# Schematic.net
KiCad netlist of a schematic drawn in EAGLE
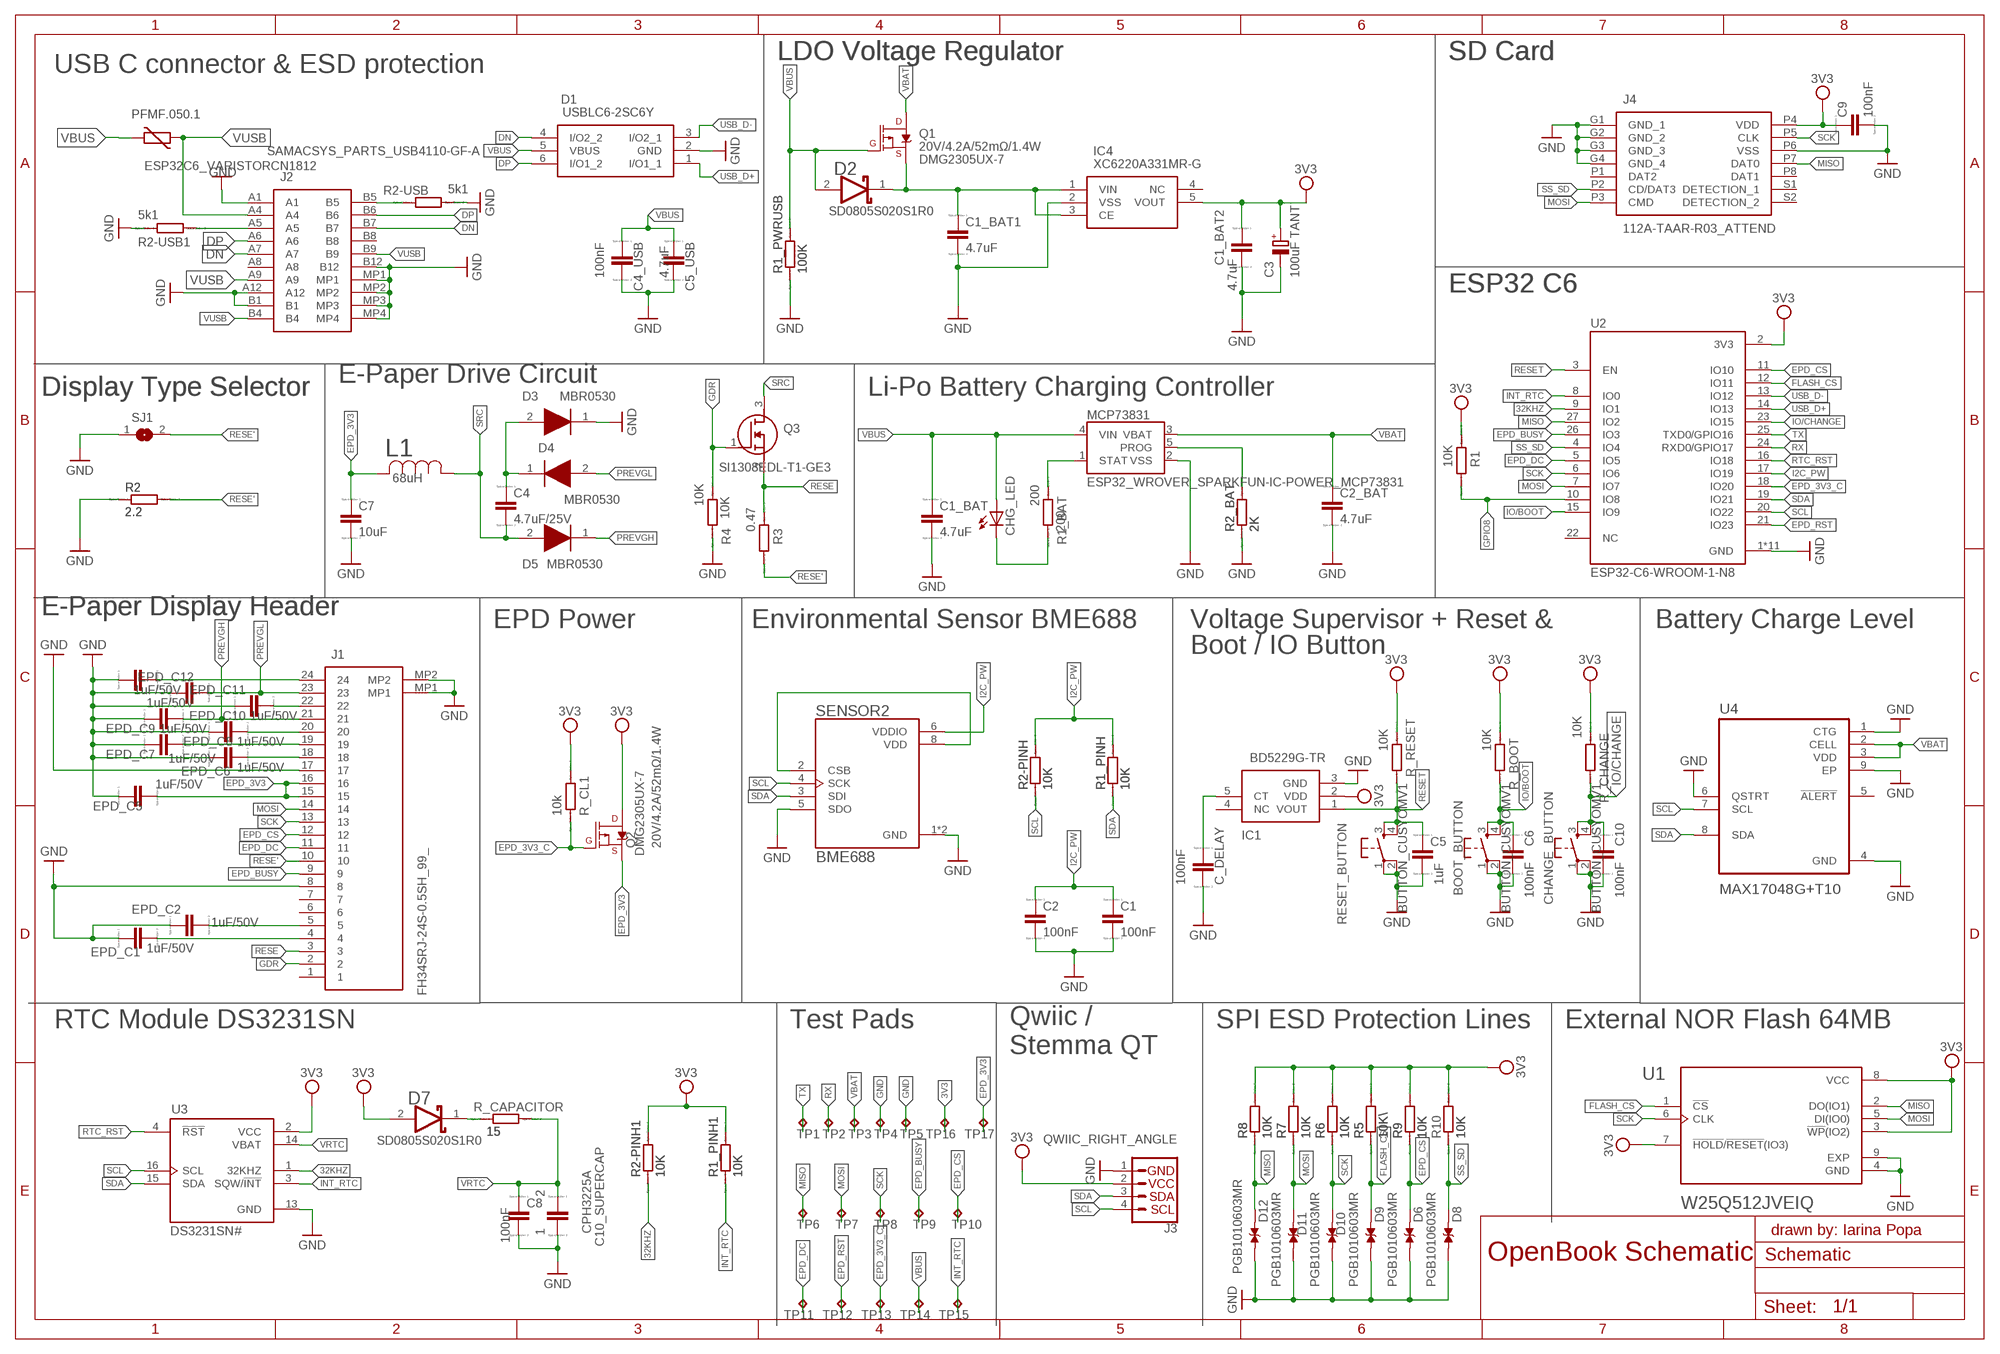
[diagram p0: schematic, sheet 1]

(export (version "E")
  (design (tool "Eeschema 10.0.6"))
  (components
    (comp (ref "BOOT_BUTTON")
      (value "BUTTON_CUSYOMV1")
      (footprint "eagle-import:MYBUTTON")
      (libsource (lib "eagle-import") (part "BUTTON_CUSYOMV1"))
    )
    (comp (ref "C1")
      (value "100nF")
      (footprint "eagle-import:EAGLE-LTSPICE_C0402")
      (libsource (lib "eagle-import") (part "EAGLE-LTSPICE_CC0402"))
    )
    (comp (ref "C1_BAT")
      (value "4.7uF")
      (footprint "eagle-import:EAGLE-LTSPICE_C0402")
      (libsource (lib "eagle-import") (part "EAGLE-LTSPICE_CC0402"))
    )
    (comp (ref "C1_BAT1")
      (value "4.7uF")
      (footprint "eagle-import:EAGLE-LTSPICE_C0402")
      (libsource (lib "eagle-import") (part "EAGLE-LTSPICE_CC0402"))
    )
    (comp (ref "C1_BAT2")
      (value "4.7uF")
      (footprint "eagle-import:EAGLE-LTSPICE_C0402")
      (libsource (lib "eagle-import") (part "EAGLE-LTSPICE_CC0402"))
    )
    (comp (ref "C2")
      (value "100nF")
      (footprint "eagle-import:EAGLE-LTSPICE_C0402")
      (libsource (lib "eagle-import") (part "EAGLE-LTSPICE_CC0402"))
    )
    (comp (ref "C2_BAT")
      (value "4.7uF")
      (footprint "eagle-import:EAGLE-LTSPICE_C0402")
      (libsource (lib "eagle-import") (part "EAGLE-LTSPICE_CC0402"))
    )
    (comp (ref "C3")
      (value "100uF TANT")
      (footprint "eagle-import:RCL_CT3528")
      (libsource (lib "eagle-import") (part "RCL_CPOL-EUCT3528"))
    )
    (comp (ref "C4")
      (value "4.7uF/25V")
      (footprint "eagle-import:EAGLE-LTSPICE_C0402")
      (libsource (lib "eagle-import") (part "EAGLE-LTSPICE_CC0402"))
    )
    (comp (ref "C4_USB")
      (value "100nF")
      (footprint "eagle-import:EAGLE-LTSPICE_C0402")
      (libsource (lib "eagle-import") (part "EAGLE-LTSPICE_CC0402"))
    )
    (comp (ref "C5")
      (value "1uF")
      (footprint "eagle-import:EAGLE-LTSPICE_C0402")
      (libsource (lib "eagle-import") (part "EAGLE-LTSPICE_CC0402"))
    )
    (comp (ref "C5_USB")
      (value "4.7uF")
      (footprint "eagle-import:EAGLE-LTSPICE_C0402")
      (libsource (lib "eagle-import") (part "EAGLE-LTSPICE_CC0402"))
    )
    (comp (ref "C6")
      (value "100nF")
      (footprint "eagle-import:EAGLE-LTSPICE_C0402")
      (libsource (lib "eagle-import") (part "EAGLE-LTSPICE_CC0402"))
    )
    (comp (ref "C7")
      (value "10uF")
      (footprint "eagle-import:EAGLE-LTSPICE_C0402")
      (libsource (lib "eagle-import") (part "EAGLE-LTSPICE_CC0402"))
    )
    (comp (ref "C8")
      (value "100nF")
      (footprint "eagle-import:EAGLE-LTSPICE_C0402")
      (libsource (lib "eagle-import") (part "EAGLE-LTSPICE_CC0402"))
    )
    (comp (ref "C9")
      (value "100nF")
      (footprint "eagle-import:EAGLE-LTSPICE_C0402")
      (libsource (lib "eagle-import") (part "EAGLE-LTSPICE_CC0402"))
    )
    (comp (ref "C10")
      (value "100nF")
      (footprint "eagle-import:EAGLE-LTSPICE_C0402")
      (libsource (lib "eagle-import") (part "EAGLE-LTSPICE_CC0402"))
    )
    (comp (ref "C10_SUPERCAP")
      (value "CPH3225A")
      (footprint "eagle-import:EAGLE-LTSPICE_C0402")
      (libsource (lib "eagle-import") (part "EAGLE-LTSPICE_CC0402"))
    )
    (comp (ref "CHANGE_BUTTON")
      (value "BUTTON_CUSYOMV1")
      (footprint "eagle-import:MYBUTTON")
      (libsource (lib "eagle-import") (part "BUTTON_CUSYOMV1"))
    )
    (comp (ref "CHG_LED")
      (value "ADAFRUIT_LEDCHIP-LED0603")
      (footprint "eagle-import:ADAFRUIT_CHIP-LED0603")
      (libsource (lib "eagle-import") (part "ADAFRUIT_LEDCHIP-LED0603"))
    )
    (comp (ref "C_DELAY")
      (value "100nF")
      (footprint "eagle-import:EAGLE-LTSPICE_C0402")
      (libsource (lib "eagle-import") (part "EAGLE-LTSPICE_CC0402"))
    )
    (comp (ref "D1")
      (value "USBLC6-2SC6Y")
      (footprint "eagle-import:SOT95P280X145-6N")
      (fields (field (name "MF") "STMicroelectronics"))
      (libsource (lib "eagle-import") (part "USBLC6-2SC6Y"))
    )
    (comp (ref "D2")
      (value "ESP32_WROVER_AVX---SD0805S020S1R0_AVX_SD0805S020S1R0_0_0AVX_SD0805S020S1R0_0_0")
      (footprint "eagle-import:ESP32_WROVER_AVX---SD0805S020S1R0_AVX_SD0805S020S1R0_0")
      (fields
        (field (name "DIGIKEY_PART_NUMBER") "478-7800-1-ND")
        (field (name "MF") "AVX")
        (field (name "MOUSER_PART_NUMBER") "581-SD0805S020S1R0")
      )
      (libsource (lib "eagle-import") (part "ESP32_WROVER_AVX---SD0805S020S1R0_AVX_SD0805S020S1R0_0_0AVX_SD0805S020S1R0_0_0"))
    )
    (comp (ref "D3")
      (value "MBR0530")
      (footprint "eagle-import:SOD3716X135N")
      (fields (field (name "MF") "ON Semiconductor"))
      (libsource (lib "eagle-import") (part "MBR0530"))
    )
    (comp (ref "D4")
      (value "MBR0530")
      (footprint "eagle-import:SOD3716X135N")
      (fields (field (name "MF") "ON Semiconductor"))
      (libsource (lib "eagle-import") (part "MBR0530"))
    )
    (comp (ref "D5")
      (value "MBR0530")
      (footprint "eagle-import:SOD3716X135N")
      (fields (field (name "MF") "ON Semiconductor"))
      (libsource (lib "eagle-import") (part "MBR0530"))
    )
    (comp (ref "D6")
      (value "PGB1010603MR")
      (footprint "eagle-import:DIOC1608X36N")
      (fields (field (name "MF") "Littelfuse Inc."))
      (libsource (lib "eagle-import") (part "PGB1010603MR"))
    )
    (comp (ref "D7")
      (value "ESP32_WROVER_AVX---SD0805S020S1R0_AVX_SD0805S020S1R0_0_0AVX_SD0805S020S1R0_0_0")
      (footprint "eagle-import:ESP32_WROVER_AVX---SD0805S020S1R0_AVX_SD0805S020S1R0_0")
      (fields
        (field (name "DIGIKEY_PART_NUMBER") "478-7800-1-ND")
        (field (name "MF") "AVX")
        (field (name "MOUSER_PART_NUMBER") "581-SD0805S020S1R0")
      )
      (libsource (lib "eagle-import") (part "ESP32_WROVER_AVX---SD0805S020S1R0_AVX_SD0805S020S1R0_0_0AVX_SD0805S020S1R0_0_0"))
    )
    (comp (ref "D8")
      (value "PGB1010603MR")
      (footprint "eagle-import:DIOC1608X36N")
      (fields (field (name "MF") "Littelfuse Inc."))
      (libsource (lib "eagle-import") (part "PGB1010603MR"))
    )
    (comp (ref "D9")
      (value "PGB1010603MR")
      (footprint "eagle-import:DIOC1608X36N")
      (fields (field (name "MF") "Littelfuse Inc."))
      (libsource (lib "eagle-import") (part "PGB1010603MR"))
    )
    (comp (ref "D10")
      (value "PGB1010603MR")
      (footprint "eagle-import:DIOC1608X36N")
      (fields (field (name "MF") "Littelfuse Inc."))
      (libsource (lib "eagle-import") (part "PGB1010603MR"))
    )
    (comp (ref "D11")
      (value "PGB1010603MR")
      (footprint "eagle-import:DIOC1608X36N")
      (fields (field (name "MF") "Littelfuse Inc."))
      (libsource (lib "eagle-import") (part "PGB1010603MR"))
    )
    (comp (ref "D12")
      (value "PGB1010603MR")
      (footprint "eagle-import:DIOC1608X36N")
      (fields (field (name "MF") "Littelfuse Inc."))
      (libsource (lib "eagle-import") (part "PGB1010603MR"))
    )
    (comp (ref "EPD_C1")
      (value "1uF/50V")
      (footprint "eagle-import:EAGLE-LTSPICE_C0402")
      (libsource (lib "eagle-import") (part "EAGLE-LTSPICE_CC0402"))
    )
    (comp (ref "EPD_C2")
      (value "1uF/50V")
      (footprint "eagle-import:EAGLE-LTSPICE_C0402")
      (libsource (lib "eagle-import") (part "EAGLE-LTSPICE_CC0402"))
    )
    (comp (ref "EPD_C5")
      (value "1uF/50V")
      (footprint "eagle-import:EAGLE-LTSPICE_C0402")
      (libsource (lib "eagle-import") (part "EAGLE-LTSPICE_CC0402"))
    )
    (comp (ref "EPD_C6")
      (value "1uF/50V")
      (footprint "eagle-import:EAGLE-LTSPICE_C0402")
      (libsource (lib "eagle-import") (part "EAGLE-LTSPICE_CC0402"))
    )
    (comp (ref "EPD_C7")
      (value "1uF/50V")
      (footprint "eagle-import:EAGLE-LTSPICE_C0402")
      (libsource (lib "eagle-import") (part "EAGLE-LTSPICE_CC0402"))
    )
    (comp (ref "EPD_C8")
      (value "1uF/50V")
      (footprint "eagle-import:EAGLE-LTSPICE_C0402")
      (libsource (lib "eagle-import") (part "EAGLE-LTSPICE_CC0402"))
    )
    (comp (ref "EPD_C9")
      (value "1uF/50V")
      (footprint "eagle-import:EAGLE-LTSPICE_C0402")
      (libsource (lib "eagle-import") (part "EAGLE-LTSPICE_CC0402"))
    )
    (comp (ref "EPD_C10")
      (value "1uF/50V")
      (footprint "eagle-import:EAGLE-LTSPICE_C0402")
      (libsource (lib "eagle-import") (part "EAGLE-LTSPICE_CC0402"))
    )
    (comp (ref "EPD_C11")
      (value "1uF/50V")
      (footprint "eagle-import:EAGLE-LTSPICE_C0402")
      (libsource (lib "eagle-import") (part "EAGLE-LTSPICE_CC0402"))
    )
    (comp (ref "EPD_C12")
      (value "1uF/50V")
      (footprint "eagle-import:EAGLE-LTSPICE_C0402")
      (libsource (lib "eagle-import") (part "EAGLE-LTSPICE_CC0402"))
    )
    (comp (ref "IC1")
      (value "BD5229G-TR")
      (footprint "eagle-import:SOT95P280X125-5N")
      (fields (field (name "MOUSER_PART_NUMBER") "755-BD5229G-TR"))
      (libsource (lib "eagle-import") (part "BD5229G-TR"))
    )
    (comp (ref "IC4")
      (value "XC6220A331MR-G")
      (footprint "eagle-import:SOT95P280X120-5N")
      (fields (field (name "MOUSER_PART_NUMBER") "865-XC6220A331MR-G"))
      (libsource (lib "eagle-import") (part "XC6220A331MR-G"))
    )
    (comp (ref "J1")
      (value "FH34SRJ-24S-0.5SH_99_")
      (footprint "eagle-import:FH34SRJ24S05SH99")
      (fields
        (field (name "MANUFACTURER_PART_NUMBER") "FH34SRJ-24S-0.5SH(99)")
        (field (name "MOUSER_PART_NUMBER") "798-FH34SRJ24S05SH99")
      )
      (libsource (lib "eagle-import") (part "FH34SRJ-24S-0.5SH_99_"))
    )
    (comp (ref "J2")
      (value "SAMACSYS_PARTS_USB4110-GF-A")
      (footprint "eagle-import:SAMACSYS_PARTS_USB4110GFA")
      (fields
        (field (name "MANUFACTURER_PART_NUMBER") "USB4110-GF-A")
        (field (name "MOUSER_PART_NUMBER") "640-USB4110-GF-A")
      )
      (libsource (lib "eagle-import") (part "SAMACSYS_PARTS_USB4110-GF-A"))
    )
    (comp (ref "J3")
      (value "QWIIC_RIGHT_ANGLE")
      (footprint "eagle-import:JST04_1MM_RA")
      (libsource (lib "eagle-import") (part "QWIIC_CONNECTORJS-1MM"))
    )
    (comp (ref "J4")
      (value "112A-TAAR-R03_ATTEND")
      (footprint "eagle-import:112ATAARR03ATTEND")
      (fields (field (name "MANUFACTURER_PART_NUMBER") "112A-TAAR-R03 ATTEND"))
      (libsource (lib "eagle-import") (part "112A-TAAR-R03_ATTEND"))
    )
    (comp (ref "L1")
      (value "68uH")
      (footprint "eagle-import:IND_4828-WE-TPC_WRE")
      (fields
        (field (name "MANUFACTURER_PART_NUMBER") "744043680")
        (field (name "COPYRIGHT") "Copyright (C) 2024 Ultra Librarian. All rights reserved.")
      )
      (libsource (lib "eagle-import") (part "744043680IND_4828-WE-TPC_WRE"))
    )
    (comp (ref "MCP73831")
      (value "ESP32_WROVER_SPARKFUN-IC-POWER_MCP73831")
      (footprint "eagle-import:ESP32_WROVER_SPARKFUN-IC-POWER_SOT23-5")
      (libsource (lib "eagle-import") (part "ESP32_WROVER_SPARKFUN-IC-POWER_MCP73831"))
    )
    (comp (ref "PFMF.050.1")
      (value "ESP32C6_VARISTORCN1812")
      (footprint "eagle-import:ESP32C6_VARISTOR_CT_CN1812")
      (libsource (lib "eagle-import") (part "ESP32C6_VARISTORCN1812"))
    )
    (comp (ref "Q1")
      (value "20V/4.2A/52mΩ/1.4W")
      (footprint "eagle-import:ESP32_WROVER_SPARKFUN-DISCRETESEMI_SOT23-3")
      (libsource (lib "eagle-import") (part "ESP32_WROVER_SPARKFUN-DISCRETESEMI_MOSFET_PCH-DMG2305UX-7"))
    )
    (comp (ref "Q2")
      (value "20V/4.2A/52mΩ/1.4W")
      (footprint "eagle-import:ESP32_WROVER_SPARKFUN-DISCRETESEMI_SOT23-3")
      (libsource (lib "eagle-import") (part "ESP32_WROVER_SPARKFUN-DISCRETESEMI_MOSFET_PCH-DMG2305UX-7"))
    )
    (comp (ref "Q3")
      (value "SI1308EDL-T1-GE3")
      (footprint "eagle-import:SOT65P210X110-3N")
      (fields (field (name "MF") "Vishay Siliconix"))
      (libsource (lib "eagle-import") (part "SI1308EDL-T1-GE3"))
    )
    (comp (ref "R1")
      (value "10K")
      (footprint "eagle-import:ESP32_WROVER_EAGLE-LTSPICE_R0402")
      (libsource (lib "eagle-import") (part "ESP32_WROVER_EAGLE-LTSPICE_RR0402"))
    )
    (comp (ref "R1_BAT")
      (value "200")
      (footprint "eagle-import:ESP32_WROVER_EAGLE-LTSPICE_R0402")
      (libsource (lib "eagle-import") (part "ESP32_WROVER_EAGLE-LTSPICE_RR0402"))
    )
    (comp (ref "R1_PINH")
      (value "10K")
      (footprint "eagle-import:ESP32_WROVER_EAGLE-LTSPICE_R0402")
      (libsource (lib "eagle-import") (part "ESP32_WROVER_EAGLE-LTSPICE_RR0402"))
    )
    (comp (ref "R1_PINH1")
      (value "10K")
      (footprint "eagle-import:ESP32_WROVER_EAGLE-LTSPICE_R0402")
      (libsource (lib "eagle-import") (part "ESP32_WROVER_EAGLE-LTSPICE_RR0402"))
    )
    (comp (ref "R1_PWRUSB")
      (value "100K")
      (footprint "eagle-import:ESP32_WROVER_EAGLE-LTSPICE_R0402")
      (libsource (lib "eagle-import") (part "ESP32_WROVER_EAGLE-LTSPICE_RR0402"))
    )
    (comp (ref "R2")
      (value "2.2")
      (footprint "eagle-import:ESP32_WROVER_EAGLE-LTSPICE_R0402")
      (libsource (lib "eagle-import") (part "ESP32_WROVER_EAGLE-LTSPICE_RR0402"))
    )
    (comp (ref "R2-PINH")
      (value "10K")
      (footprint "eagle-import:ESP32_WROVER_EAGLE-LTSPICE_R0402")
      (libsource (lib "eagle-import") (part "ESP32_WROVER_EAGLE-LTSPICE_RR0402"))
    )
    (comp (ref "R2-PINH1")
      (value "10K")
      (footprint "eagle-import:ESP32_WROVER_EAGLE-LTSPICE_R0402")
      (libsource (lib "eagle-import") (part "ESP32_WROVER_EAGLE-LTSPICE_RR0402"))
    )
    (comp (ref "R2-USB")
      (value "5k1")
      (footprint "eagle-import:ESP32_WROVER_EAGLE-LTSPICE_R0402")
      (libsource (lib "eagle-import") (part "ESP32_WROVER_EAGLE-LTSPICE_RR0402"))
    )
    (comp (ref "R2-USB1")
      (value "5k1")
      (footprint "eagle-import:ESP32_WROVER_EAGLE-LTSPICE_R0402")
      (libsource (lib "eagle-import") (part "ESP32_WROVER_EAGLE-LTSPICE_RR0402"))
    )
    (comp (ref "R2_BAT")
      (value "2K")
      (footprint "eagle-import:ESP32_WROVER_EAGLE-LTSPICE_R0402")
      (libsource (lib "eagle-import") (part "ESP32_WROVER_EAGLE-LTSPICE_RR0402"))
    )
    (comp (ref "R3")
      (value "0.47")
      (footprint "eagle-import:ESP32_WROVER_EAGLE-LTSPICE_R0402")
      (libsource (lib "eagle-import") (part "ESP32_WROVER_EAGLE-LTSPICE_RR0402"))
    )
    (comp (ref "R4")
      (value "10K")
      (footprint "eagle-import:ESP32_WROVER_EAGLE-LTSPICE_R0402")
      (libsource (lib "eagle-import") (part "ESP32_WROVER_EAGLE-LTSPICE_RR0402"))
    )
    (comp (ref "R5")
      (value "10K\\")
      (footprint "eagle-import:ESP32_WROVER_EAGLE-LTSPICE_R0402")
      (libsource (lib "eagle-import") (part "ESP32_WROVER_EAGLE-LTSPICE_RR0402"))
    )
    (comp (ref "R6")
      (value "10K")
      (footprint "eagle-import:ESP32_WROVER_EAGLE-LTSPICE_R0402")
      (libsource (lib "eagle-import") (part "ESP32_WROVER_EAGLE-LTSPICE_RR0402"))
    )
    (comp (ref "R7")
      (value "10K")
      (footprint "eagle-import:ESP32_WROVER_EAGLE-LTSPICE_R0402")
      (libsource (lib "eagle-import") (part "ESP32_WROVER_EAGLE-LTSPICE_RR0402"))
    )
    (comp (ref "R8")
      (value "10K")
      (footprint "eagle-import:ESP32_WROVER_EAGLE-LTSPICE_R0402")
      (libsource (lib "eagle-import") (part "ESP32_WROVER_EAGLE-LTSPICE_RR0402"))
    )
    (comp (ref "R9")
      (value "10K")
      (footprint "eagle-import:ESP32_WROVER_EAGLE-LTSPICE_R0402")
      (libsource (lib "eagle-import") (part "ESP32_WROVER_EAGLE-LTSPICE_RR0402"))
    )
    (comp (ref "R10")
      (value "10K")
      (footprint "eagle-import:ESP32_WROVER_EAGLE-LTSPICE_R0402")
      (libsource (lib "eagle-import") (part "ESP32_WROVER_EAGLE-LTSPICE_RR0402"))
    )
    (comp (ref "RESET_BUTTON")
      (value "BUTTON_CUSYOMV1")
      (footprint "eagle-import:MYBUTTON")
      (libsource (lib "eagle-import") (part "BUTTON_CUSYOMV1"))
    )
    (comp (ref "R_BOOT")
      (value "10K")
      (footprint "eagle-import:ESP32_WROVER_EAGLE-LTSPICE_R0402")
      (libsource (lib "eagle-import") (part "ESP32_WROVER_EAGLE-LTSPICE_RR0402"))
    )
    (comp (ref "R_CAPACITOR")
      (value "15")
      (footprint "eagle-import:ESP32_WROVER_EAGLE-LTSPICE_R0402")
      (libsource (lib "eagle-import") (part "ESP32_WROVER_EAGLE-LTSPICE_RR0402"))
    )
    (comp (ref "R_CHANGE")
      (value "10K")
      (footprint "eagle-import:ESP32_WROVER_EAGLE-LTSPICE_R0402")
      (libsource (lib "eagle-import") (part "ESP32_WROVER_EAGLE-LTSPICE_RR0402"))
    )
    (comp (ref "R_CL1")
      (value "10k")
      (footprint "eagle-import:ESP32_WROVER_EAGLE-LTSPICE_R0402")
      (libsource (lib "eagle-import") (part "ESP32_WROVER_EAGLE-LTSPICE_RR0402"))
    )
    (comp (ref "R_RESET")
      (value "10K")
      (footprint "eagle-import:ESP32_WROVER_EAGLE-LTSPICE_R0402")
      (libsource (lib "eagle-import") (part "ESP32_WROVER_EAGLE-LTSPICE_RR0402"))
    )
    (comp (ref "SENSOR2")
      (value "BME688")
      (footprint "eagle-import:ESP32_WROVER_BME680_PSON80P300X300X100-8N")
      (fields (field (name "MF") "Bosch Sensortec") (field (name "MP") "BME680"))
      (libsource (lib "eagle-import") (part "ESP32_WROVER_BME680_BME680"))
    )
    (comp (ref "SJ1") (value "SJ") (footprint "eagle-import:SJ") (libsource (lib "eagle-import") (part "SJ")))
    (comp (ref "TP1")
      (value "TPTP20R")
      (footprint "eagle-import:TP20R")
      (libsource (lib "eagle-import") (part "TPTP20R"))
    )
    (comp (ref "TP2")
      (value "TPTP20R")
      (footprint "eagle-import:TP20R")
      (libsource (lib "eagle-import") (part "TPTP20R"))
    )
    (comp (ref "TP3")
      (value "TPTP20R")
      (footprint "eagle-import:TP20R")
      (libsource (lib "eagle-import") (part "TPTP20R"))
    )
    (comp (ref "TP4")
      (value "TPTP20R")
      (footprint "eagle-import:TP20R")
      (libsource (lib "eagle-import") (part "TPTP20R"))
    )
    (comp (ref "TP5")
      (value "TPTP20R")
      (footprint "eagle-import:TP20R")
      (libsource (lib "eagle-import") (part "TPTP20R"))
    )
    (comp (ref "TP6")
      (value "TPTP20R")
      (footprint "eagle-import:TP20R")
      (libsource (lib "eagle-import") (part "TPTP20R"))
    )
    (comp (ref "TP7")
      (value "TPTP20R")
      (footprint "eagle-import:TP20R")
      (libsource (lib "eagle-import") (part "TPTP20R"))
    )
    (comp (ref "TP8")
      (value "TPTP20R")
      (footprint "eagle-import:TP20R")
      (libsource (lib "eagle-import") (part "TPTP20R"))
    )
    (comp (ref "TP9")
      (value "TPTP20R")
      (footprint "eagle-import:TP20R")
      (libsource (lib "eagle-import") (part "TPTP20R"))
    )
    (comp (ref "TP10")
      (value "TPTP20R")
      (footprint "eagle-import:TP20R")
      (libsource (lib "eagle-import") (part "TPTP20R"))
    )
    (comp (ref "TP11")
      (value "TPTP20R")
      (footprint "eagle-import:TP20R")
      (libsource (lib "eagle-import") (part "TPTP20R"))
    )
    (comp (ref "TP12")
      (value "TPTP20R")
      (footprint "eagle-import:TP20R")
      (libsource (lib "eagle-import") (part "TPTP20R"))
    )
    (comp (ref "TP13")
      (value "TPTP20R")
      (footprint "eagle-import:TP20R")
      (libsource (lib "eagle-import") (part "TPTP20R"))
    )
    (comp (ref "TP14")
      (value "TPTP20R")
      (footprint "eagle-import:TP20R")
      (libsource (lib "eagle-import") (part "TPTP20R"))
    )
    (comp (ref "TP15")
      (value "TPTP20R")
      (footprint "eagle-import:TP20R")
      (libsource (lib "eagle-import") (part "TPTP20R"))
    )
    (comp (ref "TP16")
      (value "TPTP20R")
      (footprint "eagle-import:TP20R")
      (libsource (lib "eagle-import") (part "TPTP20R"))
    )
    (comp (ref "TP17")
      (value "TPTP20R")
      (footprint "eagle-import:TP20R")
      (libsource (lib "eagle-import") (part "TPTP20R"))
    )
    (comp (ref "U1")
      (value "W25Q512JVEIQ")
      (footprint "eagle-import:SON127P600X800X80-9N")
      (fields (field (name "MF") "Winbond Electronics"))
      (libsource (lib "eagle-import") (part "W25Q512JVEIQ"))
    )
    (comp (ref "U2")
      (value "ESP32-C6-WROOM-1-N8")
      (footprint "eagle-import:XCVR_ESP32-C6-WROOM-1-N8")
      (fields (field (name "MF") "Espressif Systems"))
      (libsource (lib "eagle-import") (part "ESP32-C6-WROOM-1-N8"))
    )
    (comp (ref "U3")
      (value "DS3231SN#")
      (footprint "eagle-import:SOIC127P1032X265-16N")
      (fields (field (name "MF") "Analog Devices"))
      (libsource (lib "eagle-import") (part "DS3231SN#"))
    )
    (comp (ref "U4")
      (value "MAX17048G+T10")
      (footprint "eagle-import:SON50P200X200X80-9N")
      (fields (field (name "MF") "Analog Devices"))
      (libsource (lib "eagle-import") (part "MAX17048G+T10"))
    )
  )
  (nets
    (net (code "1") (name "3V3") (class "Default")
      (node (ref "C1_BAT2") (pin "1") (pinfunction "1_1") (pintype "passive"))
      (node (ref "C3") (pin "+") (pinfunction "+_+") (pintype "passive"))
      (node (ref "C9") (pin "1") (pinfunction "1_1") (pintype "passive"))
      (node (ref "D7") (pin "2") (pinfunction "ANODE_2") (pintype "bidirectional"))
      (node (ref "IC1") (pin "2") (pinfunction "VDD_2") (pintype "bidirectional"))
      (node (ref "IC4") (pin "5") (pinfunction "VOUT_5") (pintype "bidirectional"))
      (node (ref "J3") (pin "2") (pinfunction "2_2") (pintype "power_in"))
      (node (ref "J4") (pin "P4") (pinfunction "VDD_P4") (pintype "bidirectional"))
      (node (ref "Q2") (pin "3") (pinfunction "D_3") (pintype "bidirectional"))
      (node (ref "R1") (pin "2") (pinfunction "2_2") (pintype "passive"))
      (node (ref "R10") (pin "2") (pinfunction "2_2") (pintype "passive"))
      (node (ref "R1_PINH1") (pin "2") (pinfunction "2_2") (pintype "passive"))
      (node (ref "R2-PINH1") (pin "2") (pinfunction "2_2") (pintype "passive"))
      (node (ref "R5") (pin "2") (pinfunction "2_2") (pintype "passive"))
      (node (ref "R6") (pin "2") (pinfunction "2_2") (pintype "passive"))
      (node (ref "R7") (pin "2") (pinfunction "2_2") (pintype "passive"))
      (node (ref "R8") (pin "2") (pinfunction "2_2") (pintype "passive"))
      (node (ref "R9") (pin "2") (pinfunction "2_2") (pintype "passive"))
      (node (ref "R_BOOT") (pin "2") (pinfunction "2_2") (pintype "passive"))
      (node (ref "R_CHANGE") (pin "2") (pinfunction "2_2") (pintype "passive"))
      (node (ref "R_CL1") (pin "2") (pinfunction "2_2") (pintype "passive"))
      (node (ref "R_RESET") (pin "2") (pinfunction "2_2") (pintype "passive"))
      (node (ref "TP16") (pin "TP") (pinfunction "TP_TP") (pintype "input"))
      (node (ref "U1") (pin "3") (pinfunction "~{WP}(IO2)_3") (pintype "bidirectional"))
      (node (ref "U1") (pin "7") (pinfunction "~{HOLD}/~{RESET}(IO3)_7") (pintype "bidirectional"))
      (node (ref "U1") (pin "8") (pinfunction "VCC_8") (pintype "power_in"))
      (node (ref "U2") (pin "2") (pinfunction "3V3_2") (pintype "power_in"))
      (node (ref "U3") (pin "2") (pinfunction "VCC_2") (pintype "power_in"))
    )
    (net (code "2") (name "32KHZ") (class "Default")
      (node (ref "R2-PINH1") (pin "1") (pinfunction "1_1") (pintype "passive"))
      (node (ref "U2") (pin "9") (pinfunction "IO1_9") (pintype "bidirectional"))
      (node (ref "U3") (pin "1") (pinfunction "32KHZ_1") (pintype "output"))
    )
    (net (code "3") (name "DN") (class "Default")
      (node (ref "D1") (pin "4") (pinfunction "I/O2_2_4") (pintype "bidirectional"))
      (node (ref "J2") (pin "A7") (pinfunction "A7_A7") (pintype "bidirectional"))
      (node (ref "J2") (pin "B7") (pinfunction "B7_B7") (pintype "bidirectional"))
    )
    (net (code "4") (name "DP") (class "Default")
      (node (ref "D1") (pin "6") (pinfunction "I/O1_2_6") (pintype "bidirectional"))
      (node (ref "J2") (pin "A6") (pinfunction "A6_A6") (pintype "bidirectional"))
      (node (ref "J2") (pin "B6") (pinfunction "B6_B6") (pintype "bidirectional"))
    )
    (net (code "5") (name "EPD_3V3") (class "Default")
      (node (ref "C7") (pin "1") (pinfunction "1_1") (pintype "passive"))
      (node (ref "EPD_C5") (pin "2") (pinfunction "2_2") (pintype "passive"))
      (node (ref "J1") (pin "15") (pinfunction "15_15") (pintype "bidirectional"))
      (node (ref "J1") (pin "16") (pinfunction "16_16") (pintype "bidirectional"))
      (node (ref "L1") (pin "2") (pinfunction "2_2") (pintype "passive"))
      (node (ref "Q2") (pin "2") (pinfunction "S_2") (pintype "bidirectional"))
      (node (ref "TP17") (pin "TP") (pinfunction "TP_TP") (pintype "input"))
    )
    (net (code "6") (name "EPD_3V3_C") (class "Default")
      (node (ref "Q2") (pin "1") (pinfunction "G_1") (pintype "bidirectional"))
      (node (ref "R_CL1") (pin "1") (pinfunction "1_1") (pintype "passive"))
      (node (ref "TP13") (pin "TP") (pinfunction "TP_TP") (pintype "input"))
      (node (ref "U2") (pin "18") (pinfunction "IO20_18") (pintype "bidirectional"))
    )
    (net (code "7") (name "EPD_BUSY") (class "Default")
      (node (ref "J1") (pin "9") (pinfunction "9_9") (pintype "bidirectional"))
      (node (ref "TP9") (pin "TP") (pinfunction "TP_TP") (pintype "input"))
      (node (ref "U2") (pin "26") (pinfunction "IO3_26") (pintype "bidirectional"))
    )
    (net (code "8") (name "EPD_CS") (class "Default")
      (node (ref "D6") (pin "2") (pinfunction "2_2") (pintype "passive"))
      (node (ref "J1") (pin "12") (pinfunction "12_12") (pintype "bidirectional"))
      (node (ref "R9") (pin "1") (pinfunction "1_1") (pintype "passive"))
      (node (ref "TP10") (pin "TP") (pinfunction "TP_TP") (pintype "input"))
      (node (ref "U2") (pin "11") (pinfunction "IO10_11") (pintype "bidirectional"))
    )
    (net (code "9") (name "EPD_DC") (class "Default")
      (node (ref "J1") (pin "11") (pinfunction "11_11") (pintype "bidirectional"))
      (node (ref "TP11") (pin "TP") (pinfunction "TP_TP") (pintype "input"))
      (node (ref "U2") (pin "5") (pinfunction "IO5_5") (pintype "bidirectional"))
    )
    (net (code "10") (name "EPD_RST") (class "Default")
      (node (ref "TP12") (pin "TP") (pinfunction "TP_TP") (pintype "input"))
      (node (ref "U2") (pin "21") (pinfunction "IO23_21") (pintype "bidirectional"))
    )
    (net (code "11") (name "FLASH_CS") (class "Default")
      (node (ref "D9") (pin "2") (pinfunction "2_2") (pintype "passive"))
      (node (ref "R5") (pin "1") (pinfunction "1_1") (pintype "passive"))
      (node (ref "U1") (pin "1") (pinfunction "~{CS}_1") (pintype "input"))
      (node (ref "U2") (pin "12") (pinfunction "IO11_12") (pintype "bidirectional"))
    )
    (net (code "12") (name "GDR") (class "Default")
      (node (ref "J1") (pin "2") (pinfunction "2_2") (pintype "bidirectional"))
      (node (ref "Q3") (pin "1") (pinfunction "G_1") (pintype "bidirectional"))
      (node (ref "R4") (pin "2") (pinfunction "2_2") (pintype "passive"))
    )
    (net (code "13") (name "GND") (class "Default")
      (node (ref "BOOT_BUTTON") (pin "1") (pinfunction "1_1") (pintype "passive"))
      (node (ref "BOOT_BUTTON") (pin "2") (pinfunction "2_2") (pintype "passive"))
      (node (ref "C1") (pin "2") (pinfunction "2_2") (pintype "passive"))
      (node (ref "C10") (pin "2") (pinfunction "2_2") (pintype "passive"))
      (node (ref "C10_SUPERCAP") (pin "2") (pinfunction "2_2") (pintype "passive"))
      (node (ref "C1_BAT") (pin "2") (pinfunction "2_2") (pintype "passive"))
      (node (ref "C1_BAT1") (pin "2") (pinfunction "2_2") (pintype "passive"))
      (node (ref "C1_BAT2") (pin "2") (pinfunction "2_2") (pintype "passive"))
      (node (ref "C2") (pin "2") (pinfunction "2_2") (pintype "passive"))
      (node (ref "C2_BAT") (pin "2") (pinfunction "2_2") (pintype "passive"))
      (node (ref "C3") (pin "-") (pinfunction "-_-") (pintype "passive"))
      (node (ref "C4_USB") (pin "2") (pinfunction "2_2") (pintype "passive"))
      (node (ref "C5") (pin "2") (pinfunction "2_2") (pintype "passive"))
      (node (ref "C5_USB") (pin "2") (pinfunction "2_2") (pintype "passive"))
      (node (ref "C6") (pin "2") (pinfunction "2_2") (pintype "passive"))
      (node (ref "C7") (pin "2") (pinfunction "2_2") (pintype "passive"))
      (node (ref "C8") (pin "2") (pinfunction "2_2") (pintype "passive"))
      (node (ref "C9") (pin "2") (pinfunction "2_2") (pintype "passive"))
      (node (ref "CHANGE_BUTTON") (pin "1") (pinfunction "1_1") (pintype "passive"))
      (node (ref "CHANGE_BUTTON") (pin "2") (pinfunction "2_2") (pintype "passive"))
      (node (ref "C_DELAY") (pin "2") (pinfunction "2_2") (pintype "passive"))
      (node (ref "D1") (pin "2") (pinfunction "GND_2") (pintype "bidirectional"))
      (node (ref "D10") (pin "1") (pinfunction "1_1") (pintype "passive"))
      (node (ref "D11") (pin "1") (pinfunction "1_1") (pintype "passive"))
      (node (ref "D12") (pin "1") (pinfunction "1_1") (pintype "passive"))
      (node (ref "D3") (pin "1") (pinfunction "K_1") (pintype "bidirectional"))
      (node (ref "D6") (pin "1") (pinfunction "1_1") (pintype "passive"))
      (node (ref "D8") (pin "1") (pinfunction "1_1") (pintype "passive"))
      (node (ref "D9") (pin "1") (pinfunction "1_1") (pintype "passive"))
      (node (ref "EPD_C1") (pin "1") (pinfunction "1_1") (pintype "passive"))
      (node (ref "EPD_C10") (pin "1") (pinfunction "1_1") (pintype "passive"))
      (node (ref "EPD_C11") (pin "1") (pinfunction "1_1") (pintype "passive"))
      (node (ref "EPD_C12") (pin "1") (pinfunction "1_1") (pintype "passive"))
      (node (ref "EPD_C2") (pin "1") (pinfunction "1_1") (pintype "passive"))
      (node (ref "EPD_C5") (pin "1") (pinfunction "1_1") (pintype "passive"))
      (node (ref "EPD_C6") (pin "1") (pinfunction "1_1") (pintype "passive"))
      (node (ref "EPD_C7") (pin "1") (pinfunction "1_1") (pintype "passive"))
      (node (ref "EPD_C8") (pin "1") (pinfunction "1_1") (pintype "passive"))
      (node (ref "EPD_C9") (pin "1") (pinfunction "1_1") (pintype "passive"))
      (node (ref "IC1") (pin "3") (pinfunction "GND_3") (pintype "bidirectional"))
      (node (ref "IC4") (pin "2") (pinfunction "VSS_2") (pintype "bidirectional"))
      (node (ref "J1") (pin "17") (pinfunction "17_17") (pintype "bidirectional"))
      (node (ref "J1") (pin "8") (pinfunction "8_8") (pintype "bidirectional"))
      (node (ref "J1") (pin "MP1") (pinfunction "MP1_MP1") (pintype "bidirectional"))
      (node (ref "J1") (pin "MP2") (pinfunction "MP2_MP2") (pintype "bidirectional"))
      (node (ref "J2") (pin "A1") (pinfunction "A1_A1") (pintype "bidirectional"))
      (node (ref "J2") (pin "A12") (pinfunction "A12_A12") (pintype "bidirectional"))
      (node (ref "J2") (pin "B1") (pinfunction "B1_B1") (pintype "bidirectional"))
      (node (ref "J2") (pin "B12") (pinfunction "B12_B12") (pintype "bidirectional"))
      (node (ref "J2") (pin "MP1") (pinfunction "MP1_MP1") (pintype "bidirectional"))
      (node (ref "J2") (pin "MP2") (pinfunction "MP2_MP2") (pintype "bidirectional"))
      (node (ref "J2") (pin "MP3") (pinfunction "MP3_MP3") (pintype "bidirectional"))
      (node (ref "J2") (pin "MP4") (pinfunction "MP4_MP4") (pintype "bidirectional"))
      (node (ref "J3") (pin "1") (pinfunction "1_1") (pintype "power_in"))
      (node (ref "J4") (pin "G1") (pinfunction "GND_1_G1") (pintype "bidirectional"))
      (node (ref "J4") (pin "G2") (pinfunction "GND_2_G2") (pintype "bidirectional"))
      (node (ref "J4") (pin "G3") (pinfunction "GND_3_G3") (pintype "bidirectional"))
      (node (ref "J4") (pin "G4") (pinfunction "GND_4_G4") (pintype "bidirectional"))
      (node (ref "J4") (pin "P6") (pinfunction "VSS_P6") (pintype "bidirectional"))
      (node (ref "MCP73831") (pin "2") (pinfunction "VSS_2") (pintype "power_in"))
      (node (ref "R1_PWRUSB") (pin "1") (pinfunction "1_1") (pintype "passive"))
      (node (ref "R2") (pin "1") (pinfunction "1_1") (pintype "passive"))
      (node (ref "R2-USB") (pin "2") (pinfunction "2_2") (pintype "passive"))
      (node (ref "R2-USB1") (pin "1") (pinfunction "1_1") (pintype "passive"))
      (node (ref "R2_BAT") (pin "1") (pinfunction "1_1") (pintype "passive"))
      (node (ref "R4") (pin "1") (pinfunction "1_1") (pintype "passive"))
      (node (ref "RESET_BUTTON") (pin "1") (pinfunction "1_1") (pintype "passive"))
      (node (ref "RESET_BUTTON") (pin "2") (pinfunction "2_2") (pintype "passive"))
      (node (ref "SENSOR2") (pin "1") (pinfunction "GND_1") (pintype "power_in"))
      (node (ref "SENSOR2") (pin "5") (pinfunction "SDO_5") (pintype "bidirectional"))
      (node (ref "SENSOR2") (pin "7") (pinfunction "GND_7") (pintype "power_in"))
      (node (ref "SJ1") (pin "1") (pinfunction "1_1") (pintype "passive"))
      (node (ref "TP4") (pin "TP") (pinfunction "TP_TP") (pintype "input"))
      (node (ref "TP5") (pin "TP") (pinfunction "TP_TP") (pintype "input"))
      (node (ref "U1") (pin "4") (pinfunction "GND_4") (pintype "power_in"))
      (node (ref "U1") (pin "9") (pinfunction "EXP_9") (pintype "passive"))
      (node (ref "U2") (pin "1") (pinfunction "GND_1") (pintype "power_in"))
      (node (ref "U2") (pin "28") (pinfunction "GND_28") (pintype "power_in"))
      (node (ref "U2") (pin "29_1") (pinfunction "GND_29_1") (pintype "power_in"))
      (node (ref "U2") (pin "29_2") (pinfunction "GND_29_2") (pintype "power_in"))
      (node (ref "U2") (pin "29_3") (pinfunction "GND_29_3") (pintype "power_in"))
      (node (ref "U2") (pin "29_4") (pinfunction "GND_29_4") (pintype "power_in"))
      (node (ref "U2") (pin "29_5") (pinfunction "GND_29_5") (pintype "power_in"))
      (node (ref "U2") (pin "29_6") (pinfunction "GND_29_6") (pintype "power_in"))
      (node (ref "U2") (pin "29_7") (pinfunction "GND_29_7") (pintype "power_in"))
      (node (ref "U2") (pin "29_8") (pinfunction "GND_29_8") (pintype "power_in"))
      (node (ref "U2") (pin "29_9") (pinfunction "GND_29_9") (pintype "power_in"))
      (node (ref "U3") (pin "13") (pinfunction "GND_13") (pintype "power_in"))
      (node (ref "U4") (pin "1") (pinfunction "CTG_1") (pintype "power_in"))
      (node (ref "U4") (pin "4") (pinfunction "GND_4") (pintype "power_in"))
      (node (ref "U4") (pin "6") (pinfunction "QSTRT_6") (pintype "input"))
      (node (ref "U4") (pin "9") (pinfunction "EP_9") (pintype "power_in"))
    )
    (net (code "14") (name "GPIO8") (class "Default")
      (node (ref "R1") (pin "1") (pinfunction "1_1") (pintype "passive"))
      (node (ref "U2") (pin "10") (pinfunction "IO8_10") (pintype "bidirectional"))
    )
    (net (code "15") (name "I2C_PW") (class "Default")
      (node (ref "C1") (pin "1") (pinfunction "1_1") (pintype "passive"))
      (node (ref "C2") (pin "1") (pinfunction "1_1") (pintype "passive"))
      (node (ref "R1_PINH") (pin "2") (pinfunction "2_2") (pintype "passive"))
      (node (ref "R2-PINH") (pin "2") (pinfunction "2_2") (pintype "passive"))
      (node (ref "SENSOR2") (pin "6") (pinfunction "VDDIO_6") (pintype "power_in"))
      (node (ref "U2") (pin "17") (pinfunction "IO19_17") (pintype "bidirectional"))
    )
    (net (code "16") (name "INT_RTC") (class "Default")
      (node (ref "R1_PINH1") (pin "1") (pinfunction "1_1") (pintype "passive"))
      (node (ref "TP15") (pin "TP") (pinfunction "TP_TP") (pintype "input"))
      (node (ref "U2") (pin "8") (pinfunction "IO0_8") (pintype "bidirectional"))
      (node (ref "U3") (pin "3") (pinfunction "SQW/~{INT}_3") (pintype "output"))
    )
    (net (code "17") (name "IO{slash}BOOT") (class "Default")
      (node (ref "BOOT_BUTTON") (pin "3") (pinfunction "3_3") (pintype "passive"))
      (node (ref "BOOT_BUTTON") (pin "4") (pinfunction "4_4") (pintype "passive"))
      (node (ref "C6") (pin "1") (pinfunction "1_1") (pintype "passive"))
      (node (ref "R_BOOT") (pin "1") (pinfunction "1_1") (pintype "passive"))
      (node (ref "U2") (pin "15") (pinfunction "IO9_15") (pintype "bidirectional"))
    )
    (net (code "18") (name "IO{slash}CHANGE") (class "Default")
      (node (ref "C10") (pin "1") (pinfunction "1_1") (pintype "passive"))
      (node (ref "CHANGE_BUTTON") (pin "3") (pinfunction "3_3") (pintype "passive"))
      (node (ref "CHANGE_BUTTON") (pin "4") (pinfunction "4_4") (pintype "passive"))
      (node (ref "R_CHANGE") (pin "1") (pinfunction "1_1") (pintype "passive"))
      (node (ref "U2") (pin "23") (pinfunction "IO15_23") (pintype "bidirectional"))
    )
    (net (code "19") (name "MISO") (class "Default")
      (node (ref "D12") (pin "2") (pinfunction "2_2") (pintype "passive"))
      (node (ref "J4") (pin "P7") (pinfunction "DAT0_P7") (pintype "bidirectional"))
      (node (ref "R8") (pin "1") (pinfunction "1_1") (pintype "passive"))
      (node (ref "TP6") (pin "TP") (pinfunction "TP_TP") (pintype "input"))
      (node (ref "U1") (pin "2") (pinfunction "DO(IO1)_2") (pintype "bidirectional"))
      (node (ref "U2") (pin "27") (pinfunction "IO2_27") (pintype "bidirectional"))
    )
    (net (code "20") (name "MOSI") (class "Default")
      (node (ref "D11") (pin "2") (pinfunction "2_2") (pintype "passive"))
      (node (ref "J1") (pin "14") (pinfunction "14_14") (pintype "bidirectional"))
      (node (ref "J4") (pin "P3") (pinfunction "CMD_P3") (pintype "bidirectional"))
      (node (ref "R7") (pin "1") (pinfunction "1_1") (pintype "passive"))
      (node (ref "TP7") (pin "TP") (pinfunction "TP_TP") (pintype "input"))
      (node (ref "U1") (pin "5") (pinfunction "DI(IO0)_5") (pintype "bidirectional"))
      (node (ref "U2") (pin "7") (pinfunction "IO7_7") (pintype "bidirectional"))
    )
    (net (code "21") (name "Net-(CHG_LED-PadC)") (class "Default")
      (node (ref "CHG_LED") (pin "C") (pinfunction "C_C") (pintype "passive"))
      (node (ref "R1_BAT") (pin "1") (pinfunction "1_1") (pintype "passive"))
    )
    (net (code "22") (name "Net-(D2-CATHODE)") (class "Default")
      (node (ref "C1_BAT1") (pin "1") (pinfunction "1_1") (pintype "passive"))
      (node (ref "D2") (pin "1") (pinfunction "CATHODE_1") (pintype "bidirectional"))
      (node (ref "IC4") (pin "1") (pinfunction "VIN_1") (pintype "bidirectional"))
      (node (ref "IC4") (pin "3") (pinfunction "CE_3") (pintype "bidirectional"))
      (node (ref "Q1") (pin "2") (pinfunction "S_2") (pintype "bidirectional"))
    )
    (net (code "23") (name "Net-(D3-A)") (class "Default")
      (node (ref "C4") (pin "1") (pinfunction "1_1") (pintype "passive"))
      (node (ref "D3") (pin "2") (pinfunction "A_2") (pintype "bidirectional"))
      (node (ref "D4") (pin "1") (pinfunction "K_1") (pintype "bidirectional"))
    )
    (net (code "24") (name "Net-(D7-CATHODE)") (class "Default")
      (node (ref "D7") (pin "1") (pinfunction "CATHODE_1") (pintype "bidirectional"))
      (node (ref "R_CAPACITOR") (pin "1") (pinfunction "1_1") (pintype "passive"))
    )
    (net (code "25") (name "Net-(EPD_C1-Pad2)") (class "Default")
      (node (ref "EPD_C1") (pin "2") (pinfunction "2_2") (pintype "passive"))
      (node (ref "J1") (pin "4") (pinfunction "4_4") (pintype "bidirectional"))
    )
    (net (code "26") (name "Net-(EPD_C2-Pad2)") (class "Default")
      (node (ref "EPD_C2") (pin "2") (pinfunction "2_2") (pintype "passive"))
      (node (ref "J1") (pin "5") (pinfunction "5_5") (pintype "bidirectional"))
    )
    (net (code "27") (name "Net-(EPD_C6-Pad2)") (class "Default")
      (node (ref "EPD_C6") (pin "2") (pinfunction "2_2") (pintype "passive"))
      (node (ref "J1") (pin "18") (pinfunction "18_18") (pintype "bidirectional"))
    )
    (net (code "28") (name "Net-(EPD_C7-Pad2)") (class "Default")
      (node (ref "EPD_C7") (pin "2") (pinfunction "2_2") (pintype "passive"))
      (node (ref "J1") (pin "19") (pinfunction "19_19") (pintype "bidirectional"))
    )
    (net (code "29") (name "Net-(EPD_C8-Pad2)") (class "Default")
      (node (ref "EPD_C8") (pin "2") (pinfunction "2_2") (pintype "passive"))
      (node (ref "J1") (pin "20") (pinfunction "20_20") (pintype "bidirectional"))
    )
    (net (code "30") (name "Net-(EPD_C10-Pad2)") (class "Default")
      (node (ref "EPD_C10") (pin "2") (pinfunction "2_2") (pintype "passive"))
      (node (ref "J1") (pin "22") (pinfunction "22_22") (pintype "bidirectional"))
    )
    (net (code "31") (name "Net-(EPD_C12-Pad2)") (class "Default")
      (node (ref "EPD_C12") (pin "2") (pinfunction "2_2") (pintype "passive"))
      (node (ref "J1") (pin "24") (pinfunction "24_24") (pintype "bidirectional"))
    )
    (net (code "32") (name "Net-(IC1-CT)") (class "Default")
      (node (ref "C_DELAY") (pin "1") (pinfunction "1_1") (pintype "passive"))
      (node (ref "IC1") (pin "5") (pinfunction "CT_5") (pintype "bidirectional"))
    )
    (net (code "33") (name "Net-(J2-PadA5)") (class "Default")
      (node (ref "J2") (pin "A5") (pinfunction "A5_A5") (pintype "bidirectional"))
      (node (ref "R2-USB1") (pin "2") (pinfunction "2_2") (pintype "passive"))
    )
    (net (code "34") (name "Net-(J2-PadB5)") (class "Default")
      (node (ref "J2") (pin "B5") (pinfunction "B5_B5") (pintype "bidirectional"))
      (node (ref "R2-USB") (pin "1") (pinfunction "1_1") (pintype "passive"))
    )
    (net (code "35") (name "Net-(MCP73831-PROG)") (class "Default")
      (node (ref "MCP73831") (pin "5") (pinfunction "PROG_5") (pintype "input"))
      (node (ref "R2_BAT") (pin "2") (pinfunction "2_2") (pintype "passive"))
    )
    (net (code "36") (name "Net-(MCP73831-STAT)") (class "Default")
      (node (ref "MCP73831") (pin "1") (pinfunction "STAT_1") (pintype "output"))
      (node (ref "R1_BAT") (pin "2") (pinfunction "2_2") (pintype "passive"))
    )
    (net (code "37") (name "Net-(SENSOR2-CSB)") (class "Default")
      (node (ref "SENSOR2") (pin "2") (pinfunction "CSB_2") (pintype "input"))
      (node (ref "SENSOR2") (pin "8") (pinfunction "VDD_8") (pintype "power_in"))
    )
    (net (code "38") (name "PREVGH") (class "Default")
      (node (ref "D5") (pin "1") (pinfunction "K_1") (pintype "bidirectional"))
      (node (ref "EPD_C9") (pin "2") (pinfunction "2_2") (pintype "passive"))
      (node (ref "J1") (pin "21") (pinfunction "21_21") (pintype "bidirectional"))
    )
    (net (code "39") (name "PREVGL") (class "Default")
      (node (ref "D4") (pin "2") (pinfunction "A_2") (pintype "bidirectional"))
      (node (ref "EPD_C11") (pin "2") (pinfunction "2_2") (pintype "passive"))
      (node (ref "J1") (pin "23") (pinfunction "23_23") (pintype "bidirectional"))
    )
    (net (code "40") (name "RESE") (class "Default")
      (node (ref "J1") (pin "3") (pinfunction "3_3") (pintype "bidirectional"))
      (node (ref "Q3") (pin "2") (pinfunction "S_2") (pintype "bidirectional"))
      (node (ref "R3") (pin "2") (pinfunction "2_2") (pintype "passive"))
    )
    (net (code "41") (name "RESE'") (class "Default")
      (node (ref "J1") (pin "10") (pinfunction "10_10") (pintype "bidirectional"))
      (node (ref "R2") (pin "2") (pinfunction "2_2") (pintype "passive"))
      (node (ref "R3") (pin "1") (pinfunction "1_1") (pintype "passive"))
      (node (ref "SJ1") (pin "2") (pinfunction "2_2") (pintype "passive"))
    )
    (net (code "42") (name "RESET") (class "Default")
      (node (ref "C5") (pin "1") (pinfunction "1_1") (pintype "passive"))
      (node (ref "IC1") (pin "1") (pinfunction "VOUT_1") (pintype "bidirectional"))
      (node (ref "RESET_BUTTON") (pin "3") (pinfunction "3_3") (pintype "passive"))
      (node (ref "RESET_BUTTON") (pin "4") (pinfunction "4_4") (pintype "passive"))
      (node (ref "R_RESET") (pin "1") (pinfunction "1_1") (pintype "passive"))
      (node (ref "U2") (pin "3") (pinfunction "EN_3") (pintype "input"))
    )
    (net (code "43") (name "RTC_RST") (class "Default")
      (node (ref "U2") (pin "16") (pinfunction "IO18_16") (pintype "bidirectional"))
      (node (ref "U3") (pin "4") (pinfunction "~{RST}_4") (pintype "input"))
    )
    (net (code "44") (name "RX") (class "Default")
      (node (ref "TP2") (pin "TP") (pinfunction "TP_TP") (pintype "input"))
      (node (ref "U2") (pin "24") (pinfunction "RXD0/GPIO17_24") (pintype "bidirectional"))
    )
    (net (code "45") (name "SCK") (class "Default")
      (node (ref "D10") (pin "2") (pinfunction "2_2") (pintype "passive"))
      (node (ref "J1") (pin "13") (pinfunction "13_13") (pintype "bidirectional"))
      (node (ref "J4") (pin "P5") (pinfunction "CLK_P5") (pintype "bidirectional"))
      (node (ref "R6") (pin "1") (pinfunction "1_1") (pintype "passive"))
      (node (ref "TP8") (pin "TP") (pinfunction "TP_TP") (pintype "input"))
      (node (ref "U1") (pin "6") (pinfunction "CLK_6") (pintype "input"))
      (node (ref "U2") (pin "6") (pinfunction "IO6_6") (pintype "bidirectional"))
    )
    (net (code "46") (name "SCL") (class "Default")
      (node (ref "J3") (pin "4") (pinfunction "4_4") (pintype "passive"))
      (node (ref "R2-PINH") (pin "1") (pinfunction "1_1") (pintype "passive"))
      (node (ref "SENSOR2") (pin "4") (pinfunction "SCK_4") (pintype "input"))
      (node (ref "U2") (pin "20") (pinfunction "IO22_20") (pintype "bidirectional"))
      (node (ref "U3") (pin "16") (pinfunction "SCL_16") (pintype "input"))
      (node (ref "U4") (pin "7") (pinfunction "SCL_7") (pintype "input"))
    )
    (net (code "47") (name "SDA") (class "Default")
      (node (ref "J3") (pin "3") (pinfunction "3_3") (pintype "passive"))
      (node (ref "R1_PINH") (pin "1") (pinfunction "1_1") (pintype "passive"))
      (node (ref "SENSOR2") (pin "3") (pinfunction "SDI_3") (pintype "bidirectional"))
      (node (ref "U2") (pin "19") (pinfunction "IO21_19") (pintype "bidirectional"))
      (node (ref "U3") (pin "15") (pinfunction "SDA_15") (pintype "bidirectional"))
      (node (ref "U4") (pin "8") (pinfunction "SDA_8") (pintype "bidirectional"))
    )
    (net (code "48") (name "SRC") (class "Default")
      (node (ref "C4") (pin "2") (pinfunction "2_2") (pintype "passive"))
      (node (ref "D5") (pin "2") (pinfunction "A_2") (pintype "bidirectional"))
      (node (ref "L1") (pin "1") (pinfunction "1_1") (pintype "passive"))
      (node (ref "Q3") (pin "3") (pinfunction "D_3") (pintype "bidirectional"))
    )
    (net (code "49") (name "SS_SD") (class "Default")
      (node (ref "D8") (pin "2") (pinfunction "2_2") (pintype "passive"))
      (node (ref "J4") (pin "P2") (pinfunction "CD/DAT3_P2") (pintype "bidirectional"))
      (node (ref "R10") (pin "1") (pinfunction "1_1") (pintype "passive"))
      (node (ref "U2") (pin "4") (pinfunction "IO4_4") (pintype "bidirectional"))
    )
    (net (code "50") (name "TX") (class "Default")
      (node (ref "TP1") (pin "TP") (pinfunction "TP_TP") (pintype "input"))
      (node (ref "U2") (pin "25") (pinfunction "TXD0/GPIO16_25") (pintype "bidirectional"))
    )
    (net (code "51") (name "USB_D+") (class "Default")
      (node (ref "D1") (pin "1") (pinfunction "I/O1_1_1") (pintype "bidirectional"))
      (node (ref "U2") (pin "14") (pinfunction "IO13_14") (pintype "bidirectional"))
    )
    (net (code "52") (name "USB_D-") (class "Default")
      (node (ref "D1") (pin "3") (pinfunction "I/O2_1_3") (pintype "bidirectional"))
      (node (ref "U2") (pin "13") (pinfunction "IO12_13") (pintype "bidirectional"))
    )
    (net (code "53") (name "VBAT") (class "Default")
      (node (ref "C2_BAT") (pin "1") (pinfunction "1_1") (pintype "passive"))
      (node (ref "MCP73831") (pin "3") (pinfunction "VBAT_3") (pintype "power_in"))
      (node (ref "Q1") (pin "3") (pinfunction "D_3") (pintype "bidirectional"))
      (node (ref "TP3") (pin "TP") (pinfunction "TP_TP") (pintype "input"))
      (node (ref "U4") (pin "2") (pinfunction "CELL_2") (pintype "power_in"))
      (node (ref "U4") (pin "3") (pinfunction "VDD_3") (pintype "power_in"))
    )
    (net (code "54") (name "VBUS") (class "Default")
      (node (ref "C1_BAT") (pin "1") (pinfunction "1_1") (pintype "passive"))
      (node (ref "C4_USB") (pin "1") (pinfunction "1_1") (pintype "passive"))
      (node (ref "C5_USB") (pin "1") (pinfunction "1_1") (pintype "passive"))
      (node (ref "CHG_LED") (pin "A") (pinfunction "A_A") (pintype "passive"))
      (node (ref "D1") (pin "5") (pinfunction "VBUS_5") (pintype "bidirectional"))
      (node (ref "D2") (pin "2") (pinfunction "ANODE_2") (pintype "bidirectional"))
      (node (ref "MCP73831") (pin "4") (pinfunction "VIN_4") (pintype "power_in"))
      (node (ref "PFMF.050.1") (pin "2") (pinfunction "2_2") (pintype "passive"))
      (node (ref "Q1") (pin "1") (pinfunction "G_1") (pintype "bidirectional"))
      (node (ref "R1_PWRUSB") (pin "2") (pinfunction "2_2") (pintype "passive"))
      (node (ref "TP14") (pin "TP") (pinfunction "TP_TP") (pintype "input"))
    )
    (net (code "55") (name "VRTC") (class "Default")
      (node (ref "C10_SUPERCAP") (pin "1") (pinfunction "1_1") (pintype "passive"))
      (node (ref "C8") (pin "1") (pinfunction "1_1") (pintype "passive"))
      (node (ref "R_CAPACITOR") (pin "2") (pinfunction "2_2") (pintype "passive"))
      (node (ref "U3") (pin "14") (pinfunction "VBAT_14") (pintype "power_in"))
    )
    (net (code "56") (name "VUSB") (class "Default")
      (node (ref "J2") (pin "A4") (pinfunction "A4_A4") (pintype "bidirectional"))
      (node (ref "J2") (pin "A9") (pinfunction "A9_A9") (pintype "bidirectional"))
      (node (ref "J2") (pin "B4") (pinfunction "B4_B4") (pintype "bidirectional"))
      (node (ref "J2") (pin "B9") (pinfunction "B9_B9") (pintype "bidirectional"))
      (node (ref "PFMF.050.1") (pin "1") (pinfunction "1_1") (pintype "passive"))
    )
    (net (code "57") (name "unconnected-(IC1-NC-Pad4)") (class "Default")
      (node (ref "IC1") (pin "4") (pinfunction "NC_4") (pintype "no_connect"))
    )
    (net (code "58") (name "unconnected-(IC4-NC-Pad4)") (class "Default")
      (node (ref "IC4") (pin "4") (pinfunction "NC_4") (pintype "no_connect"))
    )
    (net (code "59") (name "unconnected-(J1-Pad1)") (class "Default")
      (node (ref "J1") (pin "1") (pinfunction "1_1") (pintype "bidirectional"))
    )
    (net (code "60") (name "unconnected-(J1-Pad6)") (class "Default")
      (node (ref "J1") (pin "6") (pinfunction "6_6") (pintype "bidirectional"))
    )
    (net (code "61") (name "unconnected-(J1-Pad7)") (class "Default")
      (node (ref "J1") (pin "7") (pinfunction "7_7") (pintype "bidirectional"))
    )
    (net (code "62") (name "unconnected-(J2-PadA8)") (class "Default")
      (node (ref "J2") (pin "A8") (pinfunction "A8_A8") (pintype "bidirectional"))
    )
    (net (code "63") (name "unconnected-(J2-PadB8)") (class "Default")
      (node (ref "J2") (pin "B8") (pinfunction "B8_B8") (pintype "bidirectional"))
    )
    (net (code "64") (name "unconnected-(J4-DAT1-PadP8)") (class "Default")
      (node (ref "J4") (pin "P8") (pinfunction "DAT1_P8") (pintype "bidirectional"))
    )
    (net (code "65") (name "unconnected-(J4-DAT2-PadP1)") (class "Default")
      (node (ref "J4") (pin "P1") (pinfunction "DAT2_P1") (pintype "bidirectional"))
    )
    (net (code "66") (name "unconnected-(J4-DETECTION_1-PadS1)") (class "Default")
      (node (ref "J4") (pin "S1") (pinfunction "DETECTION_1_S1") (pintype "bidirectional"))
    )
    (net (code "67") (name "unconnected-(J4-DETECTION_2-PadS2)") (class "Default")
      (node (ref "J4") (pin "S2") (pinfunction "DETECTION_2_S2") (pintype "bidirectional"))
    )
    (net (code "68") (name "unconnected-(U2-NC-Pad22)") (class "Default")
      (node (ref "U2") (pin "22") (pinfunction "NC_22") (pintype "no_connect"))
    )
    (net (code "69") (name "unconnected-(U4-~{ALERT}-Pad5)") (class "Default")
      (node (ref "U4") (pin "5") (pinfunction "~{ALERT}_5") (pintype "output"))
    )
  )
)
